# Interface_CoVASPSy_v1re2.net
KiCad netlist of a schematic drawn in EAGLE
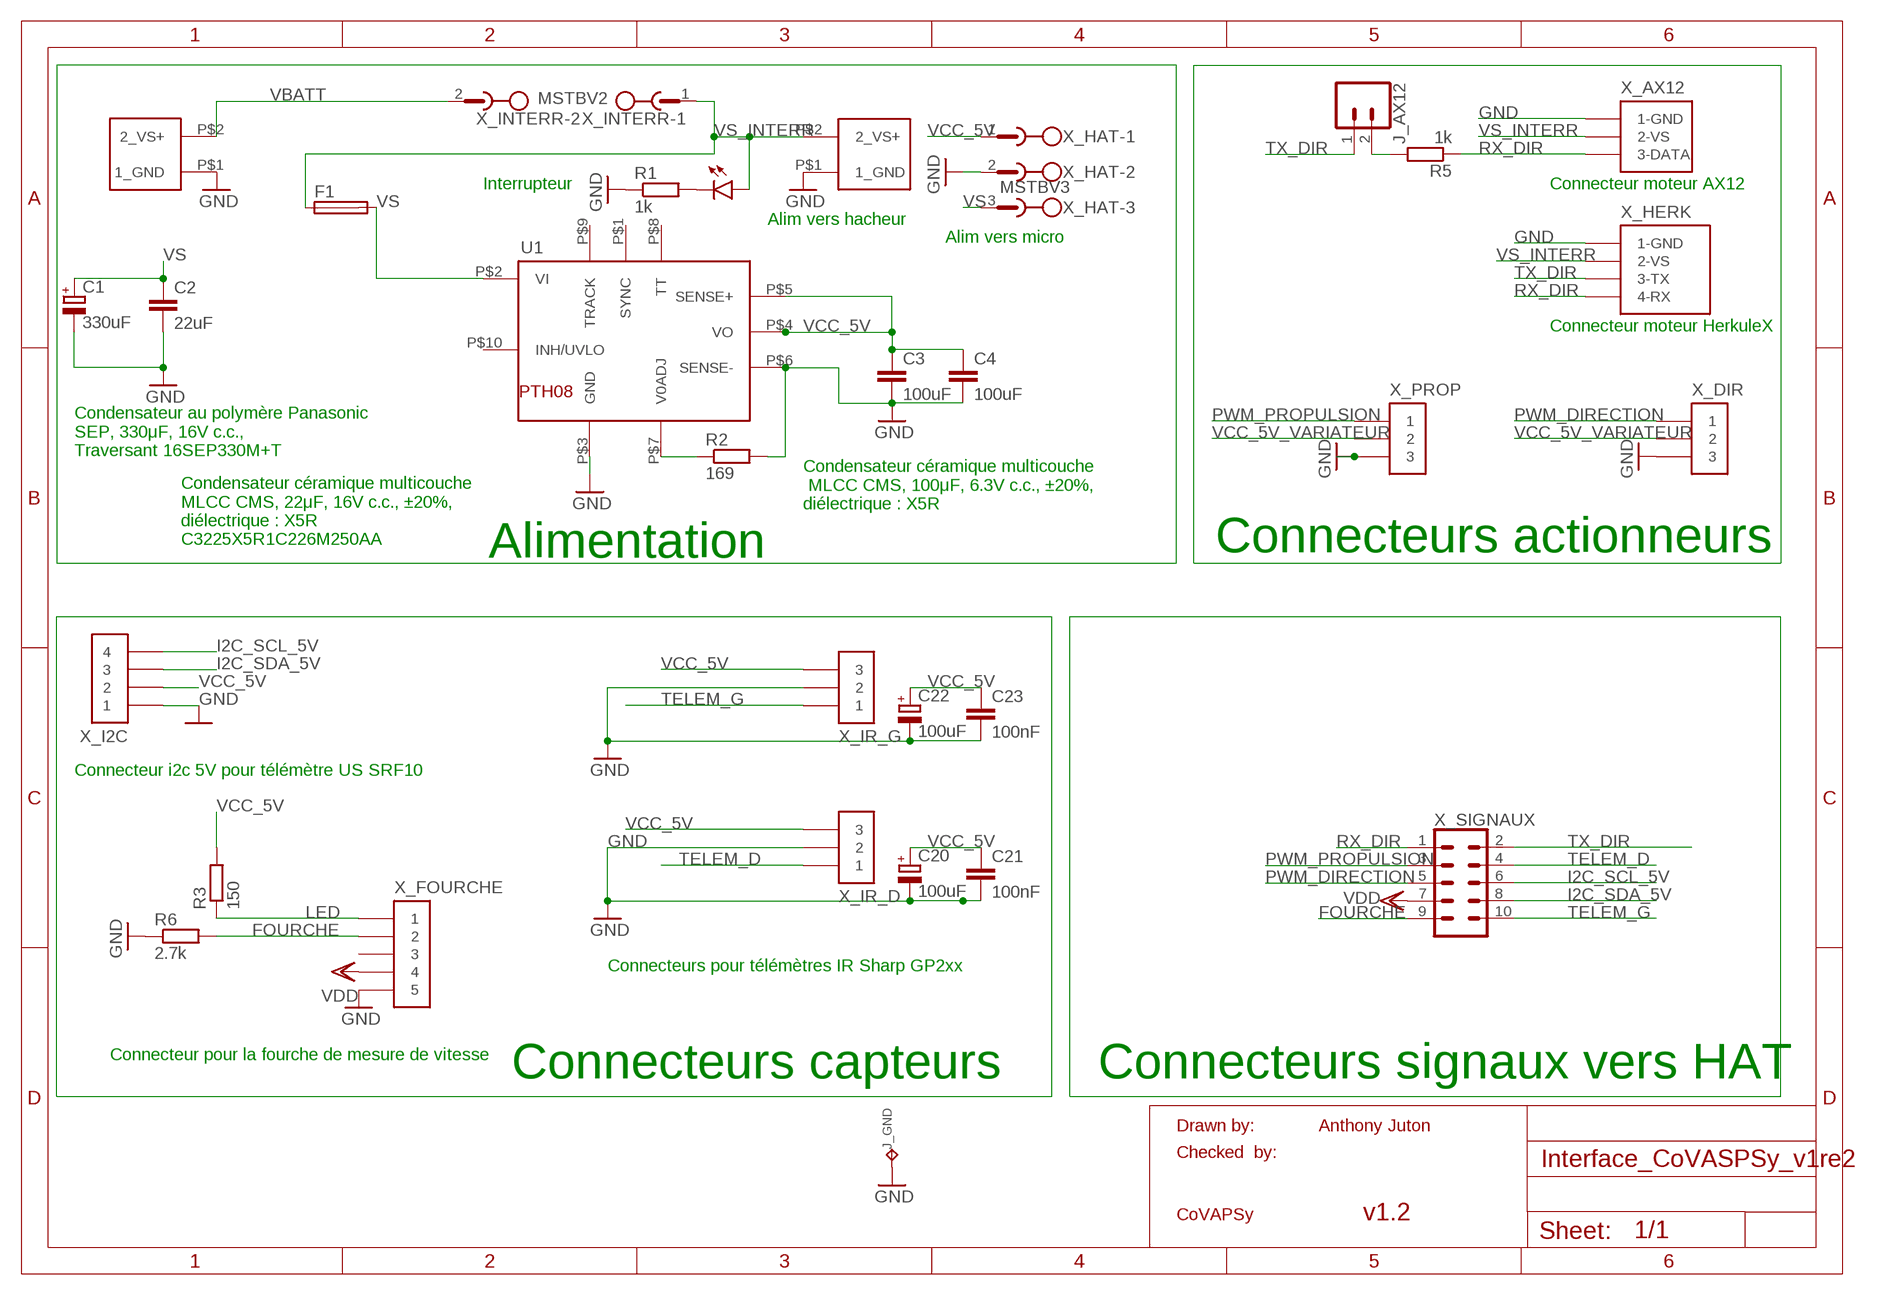
[diagram p0: schematic, sheet 1]

(export (version "E")
  (design (tool "Eeschema 10.0.6"))
  (components
    (comp (ref "C1")
      (value "330uF")
      (footprint "eagle-import:E3,5-10")
      (libsource (lib "eagle-import") (part "rcl_334_CPOL-EUE3.5-10"))
    )
    (comp (ref "C2")
      (value "22uF")
      (footprint "eagle-import:C1210")
      (libsource (lib "eagle-import") (part "rcl_334_C-EUC1210"))
    )
    (comp (ref "C3")
      (value "100uF")
      (footprint "eagle-import:C1206K")
      (libsource (lib "eagle-import") (part "C-EUC1206K"))
    )
    (comp (ref "C4")
      (value "100uF")
      (footprint "eagle-import:C1206K")
      (libsource (lib "eagle-import") (part "C-EUC1206K"))
    )
    (comp (ref "C20")
      (value "100uF")
      (footprint "eagle-import:A_3216-18W")
      (libsource (lib "eagle-import") (part "CPOL-EUA/3216-18W"))
    )
    (comp (ref "C21")
      (value "100nF")
      (footprint "eagle-import:C1206")
      (libsource (lib "eagle-import") (part "C-EUC1206"))
    )
    (comp (ref "C22")
      (value "100uF")
      (footprint "eagle-import:A_3216-18W")
      (libsource (lib "eagle-import") (part "CPOL-EUA/3216-18W"))
    )
    (comp (ref "C23")
      (value "100nF")
      (footprint "eagle-import:C1206")
      (libsource (lib "eagle-import") (part "C-EUC1206"))
    )
    (comp (ref "F1")
      (value "SH22,5")
      (footprint "eagle-import:SH22,5")
      (fields (field (name "MF") "SCHURTER") (field (name "MPN") "0031.8201"))
      (libsource (lib "eagle-import") (part "SH22,5"))
    )
    (comp (ref "J_AX12")
      (value "CONN_02")
      (footprint "eagle-import:1X02")
      (libsource (lib "eagle-import") (part "CONN_02"))
    )
    (comp (ref "J_GND")
      (value "COSSE_POIGN")
      (footprint "eagle-import:COSSE_POIGNARD")
      (libsource (lib "eagle-import") (part "COSSE_POIGN"))
    )
    (comp (ref "LED1")
      (value "LEDSML1206")
      (footprint "eagle-import:SML1206")
      (libsource (lib "eagle-import") (part "LEDSML1206"))
    )
    (comp (ref "R1")
      (value "1k")
      (footprint "eagle-import:M1206")
      (libsource (lib "eagle-import") (part "rcl_334_R-EU_M1206"))
    )
    (comp (ref "R2")
      (value "169")
      (footprint "eagle-import:R0805")
      (libsource (lib "eagle-import") (part "rcl_334_R-EU_R0805"))
    )
    (comp (ref "R3")
      (value "150")
      (footprint "eagle-import:M1206")
      (libsource (lib "eagle-import") (part "rcl_334_R-EU_M1206"))
    )
    (comp (ref "R5")
      (value "1k")
      (footprint "eagle-import:M1206")
      (libsource (lib "eagle-import") (part "R-EU_M1206"))
    )
    (comp (ref "R6")
      (value "2.7k")
      (footprint "eagle-import:M1206")
      (libsource (lib "eagle-import") (part "rcl_334_R-EU_M1206"))
    )
    (comp (ref "U1")
      (value "CONV_TI_PTH08")
      (footprint "eagle-import:CONV_TI_PTH8")
      (libsource (lib "eagle-import") (part "CONV_TI_PTH08"))
    )
    (comp (ref "X_AX12")
      (value "MOLEX_AX12")
      (footprint "eagle-import:MOLEX_AX12")
      (libsource (lib "eagle-import") (part "MOLEX_AX12"))
    )
    (comp (ref "X_BATT")
      (value "CONN_ALIM_TROU")
      (footprint "eagle-import:CONN_ALIM_TROU")
      (libsource (lib "eagle-import") (part "CONN_ALIM_TROU"))
    )
    (comp (ref "X_DIR")
      (value "CAVALIER_3")
      (footprint "eagle-import:CAVALIER_3")
      (libsource (lib "eagle-import") (part "CAVALIER_3"))
    )
    (comp (ref "X_FOURCHE")
      (value "MOLEX_5_DROIT")
      (footprint "eagle-import:MOLEX_5_DROIT")
      (libsource (lib "eagle-import") (part "MOLEX_5_DROIT"))
    )
    (comp (ref "X_HACH")
      (value "CONN_ALIM_TROU")
      (footprint "eagle-import:CONN_ALIM_TROU")
      (libsource (lib "eagle-import") (part "CONN_ALIM_TROU"))
    )
    (comp (ref "X_HAT")
      (value "MSTBV3")
      (footprint "eagle-import:MSTBV3")
      (fields (field (name "MPN") "MSTBV 2,5/3-GF-5.08"))
      (libsource (lib "eagle-import") (part "MSTBV3"))
    )
    (comp (ref "X_HERK")
      (value "TE_HERKULEX")
      (footprint "eagle-import:TE_HERKULEX")
      (libsource (lib "eagle-import") (part "TE_HERKULEX"))
    )
    (comp (ref "X_I2C")
      (value "MOLEX_4_DROIT")
      (footprint "eagle-import:MOLEX_4_DROIT")
      (libsource (lib "eagle-import") (part "MOLEX_4_DROIT"))
    )
    (comp (ref "X_INTERR")
      (value "MSTBV2")
      (footprint "eagle-import:MSTBV2")
      (fields (field (name "MPN") "MSTBV 2,5/2-GF-5.08"))
      (libsource (lib "eagle-import") (part "MSTBV2"))
    )
    (comp (ref "X_IR_D")
      (value "JST_3")
      (footprint "eagle-import:JST_3")
      (libsource (lib "eagle-import") (part "JST_3"))
    )
    (comp (ref "X_IR_G")
      (value "JST_3")
      (footprint "eagle-import:JST_3")
      (libsource (lib "eagle-import") (part "JST_3"))
    )
    (comp (ref "X_PROP")
      (value "CAVALIER_3")
      (footprint "eagle-import:CAVALIER_3")
      (libsource (lib "eagle-import") (part "CAVALIER_3"))
    )
    (comp (ref "X_SIGNAUX")
      (value "CONN_05X2SHD")
      (footprint "eagle-import:2X5-SHROUDED")
      (libsource (lib "eagle-import") (part "CONN_05X2SHD"))
    )
  )
  (nets
    (net (code "1") (name "/FOURCHE") (class "Default")
      (node (ref "R6") (pin "2") (pinfunction "2_2") (pintype "passive"))
      (node (ref "X_FOURCHE") (pin "P$2") (pinfunction "2_P$2") (pintype "bidirectional"))
      (node (ref "X_SIGNAUX") (pin "9") (pinfunction "9_9") (pintype "passive"))
    )
    (net (code "2") (name "/I2C_SCL_5V") (class "Default")
      (node (ref "X_I2C") (pin "P$4") (pinfunction "4_P$4") (pintype "bidirectional"))
      (node (ref "X_SIGNAUX") (pin "6") (pinfunction "6_6") (pintype "passive"))
    )
    (net (code "3") (name "/I2C_SDA_5V") (class "Default")
      (node (ref "X_I2C") (pin "P$3") (pinfunction "3_P$3") (pintype "bidirectional"))
      (node (ref "X_SIGNAUX") (pin "8") (pinfunction "8_8") (pintype "passive"))
    )
    (net (code "4") (name "/LED") (class "Default")
      (node (ref "R3") (pin "1") (pinfunction "1_1") (pintype "passive"))
      (node (ref "X_FOURCHE") (pin "P$1") (pinfunction "1_P$1") (pintype "bidirectional"))
    )
    (net (code "6") (name "/PWM_DIRECTION") (class "Default")
      (node (ref "X_DIR") (pin "P$1") (pinfunction "1_P$1") (pintype "bidirectional"))
      (node (ref "X_SIGNAUX") (pin "5") (pinfunction "5_5") (pintype "passive"))
    )
    (net (code "7") (name "/PWM_PROPULSION") (class "Default")
      (node (ref "X_PROP") (pin "P$1") (pinfunction "1_P$1") (pintype "bidirectional"))
      (node (ref "X_SIGNAUX") (pin "3") (pinfunction "3_3") (pintype "passive"))
    )
    (net (code "8") (name "/RX_DIR") (class "Default")
      (node (ref "R5") (pin "1") (pinfunction "1_1") (pintype "passive"))
      (node (ref "X_AX12") (pin "P$3") (pinfunction "3-DATA_P$3") (pintype "bidirectional"))
      (node (ref "X_HERK") (pin "P$4") (pinfunction "4-RX_P$4") (pintype "bidirectional"))
      (node (ref "X_SIGNAUX") (pin "1") (pinfunction "1_1") (pintype "passive"))
    )
    (net (code "9") (name "/TELEM_D") (class "Default")
      (node (ref "X_IR_D") (pin "P$1") (pinfunction "1_P$1") (pintype "bidirectional"))
      (node (ref "X_SIGNAUX") (pin "4") (pinfunction "4_4") (pintype "passive"))
    )
    (net (code "10") (name "/TELEM_G") (class "Default")
      (node (ref "X_IR_G") (pin "P$1") (pinfunction "1_P$1") (pintype "bidirectional"))
      (node (ref "X_SIGNAUX") (pin "10") (pinfunction "10_10") (pintype "passive"))
    )
    (net (code "11") (name "/TX_DIR") (class "Default")
      (node (ref "J_AX12") (pin "1") (pinfunction "1_1") (pintype "passive"))
      (node (ref "X_HERK") (pin "P$3") (pinfunction "3-TX_P$3") (pintype "bidirectional"))
      (node (ref "X_SIGNAUX") (pin "2") (pinfunction "2_2") (pintype "passive"))
    )
    (net (code "12") (name "/VBATT") (class "Default")
      (node (ref "X_BATT") (pin "P$2") (pinfunction "2_VS+_P$2") (pintype "bidirectional"))
      (node (ref "X_INTERR") (pin "2") (pinfunction "1_2") (pintype "passive"))
    )
    (net (code "13") (name "/VCC_5V") (class "Default")
      (node (ref "C20") (pin "+") (pinfunction "+_+") (pintype "passive"))
      (node (ref "C21") (pin "1") (pinfunction "1_1") (pintype "passive"))
      (node (ref "C22") (pin "+") (pinfunction "+_+") (pintype "passive"))
      (node (ref "C23") (pin "1") (pinfunction "1_1") (pintype "passive"))
      (node (ref "C3") (pin "1") (pinfunction "1_1") (pintype "passive"))
      (node (ref "C4") (pin "1") (pinfunction "1_1") (pintype "passive"))
      (node (ref "R3") (pin "2") (pinfunction "2_2") (pintype "passive"))
      (node (ref "U1") (pin "P$4") (pinfunction "VO_P$4") (pintype "output"))
      (node (ref "U1") (pin "P$5") (pinfunction "SENSE+_P$5") (pintype "bidirectional"))
      (node (ref "X_HAT") (pin "1") (pinfunction "1_1") (pintype "passive"))
      (node (ref "X_I2C") (pin "P$2") (pinfunction "2_P$2") (pintype "bidirectional"))
      (node (ref "X_IR_D") (pin "P$3") (pinfunction "3_P$3") (pintype "bidirectional"))
      (node (ref "X_IR_G") (pin "P$3") (pinfunction "3_P$3") (pintype "bidirectional"))
    )
    (net (code "14") (name "/VCC_5V_VARIATEUR") (class "Default")
      (node (ref "X_DIR") (pin "P$2") (pinfunction "2_P$2") (pintype "bidirectional"))
      (node (ref "X_PROP") (pin "P$2") (pinfunction "2_P$2") (pintype "bidirectional"))
    )
    (net (code "15") (name "/VS") (class "Default")
      (node (ref "C1") (pin "+") (pinfunction "+_+") (pintype "passive"))
      (node (ref "C2") (pin "1") (pinfunction "1_1") (pintype "passive"))
      (node (ref "F1") (pin "2") (pinfunction "2_2") (pintype "passive"))
      (node (ref "U1") (pin "P$2") (pinfunction "VI_P$2") (pintype "input"))
      (node (ref "X_HAT") (pin "3") (pinfunction "1_3") (pintype "passive"))
    )
    (net (code "16") (name "/VS_INTERR") (class "Default")
      (node (ref "F1") (pin "1") (pinfunction "1_1") (pintype "passive"))
      (node (ref "LED1") (pin "A") (pinfunction "A_A") (pintype "passive"))
      (node (ref "X_AX12") (pin "P$2") (pinfunction "2-VS_P$2") (pintype "bidirectional"))
      (node (ref "X_HACH") (pin "P$2") (pinfunction "2_VS+_P$2") (pintype "bidirectional"))
      (node (ref "X_HERK") (pin "P$2") (pinfunction "2-VS_P$2") (pintype "bidirectional"))
      (node (ref "X_INTERR") (pin "1") (pinfunction "1_1") (pintype "passive"))
    )
    (net (code "17") (name "GND") (class "Default")
      (node (ref "C1") (pin "-") (pinfunction "-_-") (pintype "passive"))
      (node (ref "C2") (pin "2") (pinfunction "2_2") (pintype "passive"))
      (node (ref "C20") (pin "-") (pinfunction "-_-") (pintype "passive"))
      (node (ref "C21") (pin "2") (pinfunction "2_2") (pintype "passive"))
      (node (ref "C22") (pin "-") (pinfunction "-_-") (pintype "passive"))
      (node (ref "C23") (pin "2") (pinfunction "2_2") (pintype "passive"))
      (node (ref "C3") (pin "2") (pinfunction "2_2") (pintype "passive"))
      (node (ref "C4") (pin "2") (pinfunction "2_2") (pintype "passive"))
      (node (ref "J_GND") (pin "P$1") (pinfunction "P$1_P$1") (pintype "bidirectional"))
      (node (ref "R1") (pin "1") (pinfunction "1_1") (pintype "passive"))
      (node (ref "R2") (pin "2") (pinfunction "2_2") (pintype "passive"))
      (node (ref "R6") (pin "1") (pinfunction "1_1") (pintype "passive"))
      (node (ref "U1") (pin "P$3") (pinfunction "GND_P$3") (pintype "bidirectional"))
      (node (ref "U1") (pin "P$6") (pinfunction "SENSE-_P$6") (pintype "bidirectional"))
      (node (ref "X_AX12") (pin "P$1") (pinfunction "1-GND_P$1") (pintype "bidirectional"))
      (node (ref "X_BATT") (pin "P$1") (pinfunction "1_GND_P$1") (pintype "bidirectional"))
      (node (ref "X_DIR") (pin "P$3") (pinfunction "3_P$3") (pintype "bidirectional"))
      (node (ref "X_FOURCHE") (pin "P$5") (pinfunction "5_P$5") (pintype "bidirectional"))
      (node (ref "X_HACH") (pin "P$1") (pinfunction "1_GND_P$1") (pintype "bidirectional"))
      (node (ref "X_HAT") (pin "2") (pinfunction "1_2") (pintype "passive"))
      (node (ref "X_HERK") (pin "P$1") (pinfunction "1-GND_P$1") (pintype "bidirectional"))
      (node (ref "X_I2C") (pin "P$1") (pinfunction "1_P$1") (pintype "bidirectional"))
      (node (ref "X_IR_D") (pin "P$2") (pinfunction "2_P$2") (pintype "bidirectional"))
      (node (ref "X_IR_G") (pin "P$2") (pinfunction "2_P$2") (pintype "bidirectional"))
      (node (ref "X_PROP") (pin "P$3") (pinfunction "3_P$3") (pintype "bidirectional"))
    )
    (net (code "18") (name "Net-(J_AX12-Pad2)") (class "Default")
      (node (ref "J_AX12") (pin "2") (pinfunction "2_2") (pintype "passive"))
      (node (ref "R5") (pin "2") (pinfunction "2_2") (pintype "passive"))
    )
    (net (code "19") (name "Net-(LED1-PadC)") (class "Default")
      (node (ref "LED1") (pin "C") (pinfunction "C_C") (pintype "passive"))
      (node (ref "R1") (pin "2") (pinfunction "2_2") (pintype "passive"))
    )
    (net (code "20") (name "Net-(U1-V0ADJ)") (class "Default")
      (node (ref "R2") (pin "1") (pinfunction "1_1") (pintype "passive"))
      (node (ref "U1") (pin "P$7") (pinfunction "V0ADJ_P$7") (pintype "bidirectional"))
    )
    (net (code "21") (name "VDD") (class "Default")
      (node (ref "X_FOURCHE") (pin "P$4") (pinfunction "4_P$4") (pintype "bidirectional"))
      (node (ref "X_SIGNAUX") (pin "7") (pinfunction "7_7") (pintype "passive"))
    )
    (net (code "22") (name "unconnected-(U1-INH{slash}UVLO-PadP$10)") (class "Default")
      (node (ref "U1") (pin "P$10") (pinfunction "INH/UVLO_P$10") (pintype "input"))
    )
    (net (code "23") (name "unconnected-(U1-SYNC-PadP$1)") (class "Default")
      (node (ref "U1") (pin "P$1") (pinfunction "SYNC_P$1") (pintype "bidirectional"))
    )
    (net (code "24") (name "unconnected-(U1-TRACK-PadP$9)") (class "Default")
      (node (ref "U1") (pin "P$9") (pinfunction "TRACK_P$9") (pintype "bidirectional"))
    )
    (net (code "25") (name "unconnected-(U1-TT-PadP$8)") (class "Default")
      (node (ref "U1") (pin "P$8") (pinfunction "TT_P$8") (pintype "bidirectional"))
    )
    (net (code "26") (name "unconnected-(X_FOURCHE-3-PadP$3)") (class "Default")
      (node (ref "X_FOURCHE") (pin "P$3") (pinfunction "3_P$3") (pintype "bidirectional"))
    )
  )
)
